# Antenna_and_LoRa.net
KiCad netlist of a schematic drawn in Altium Designer
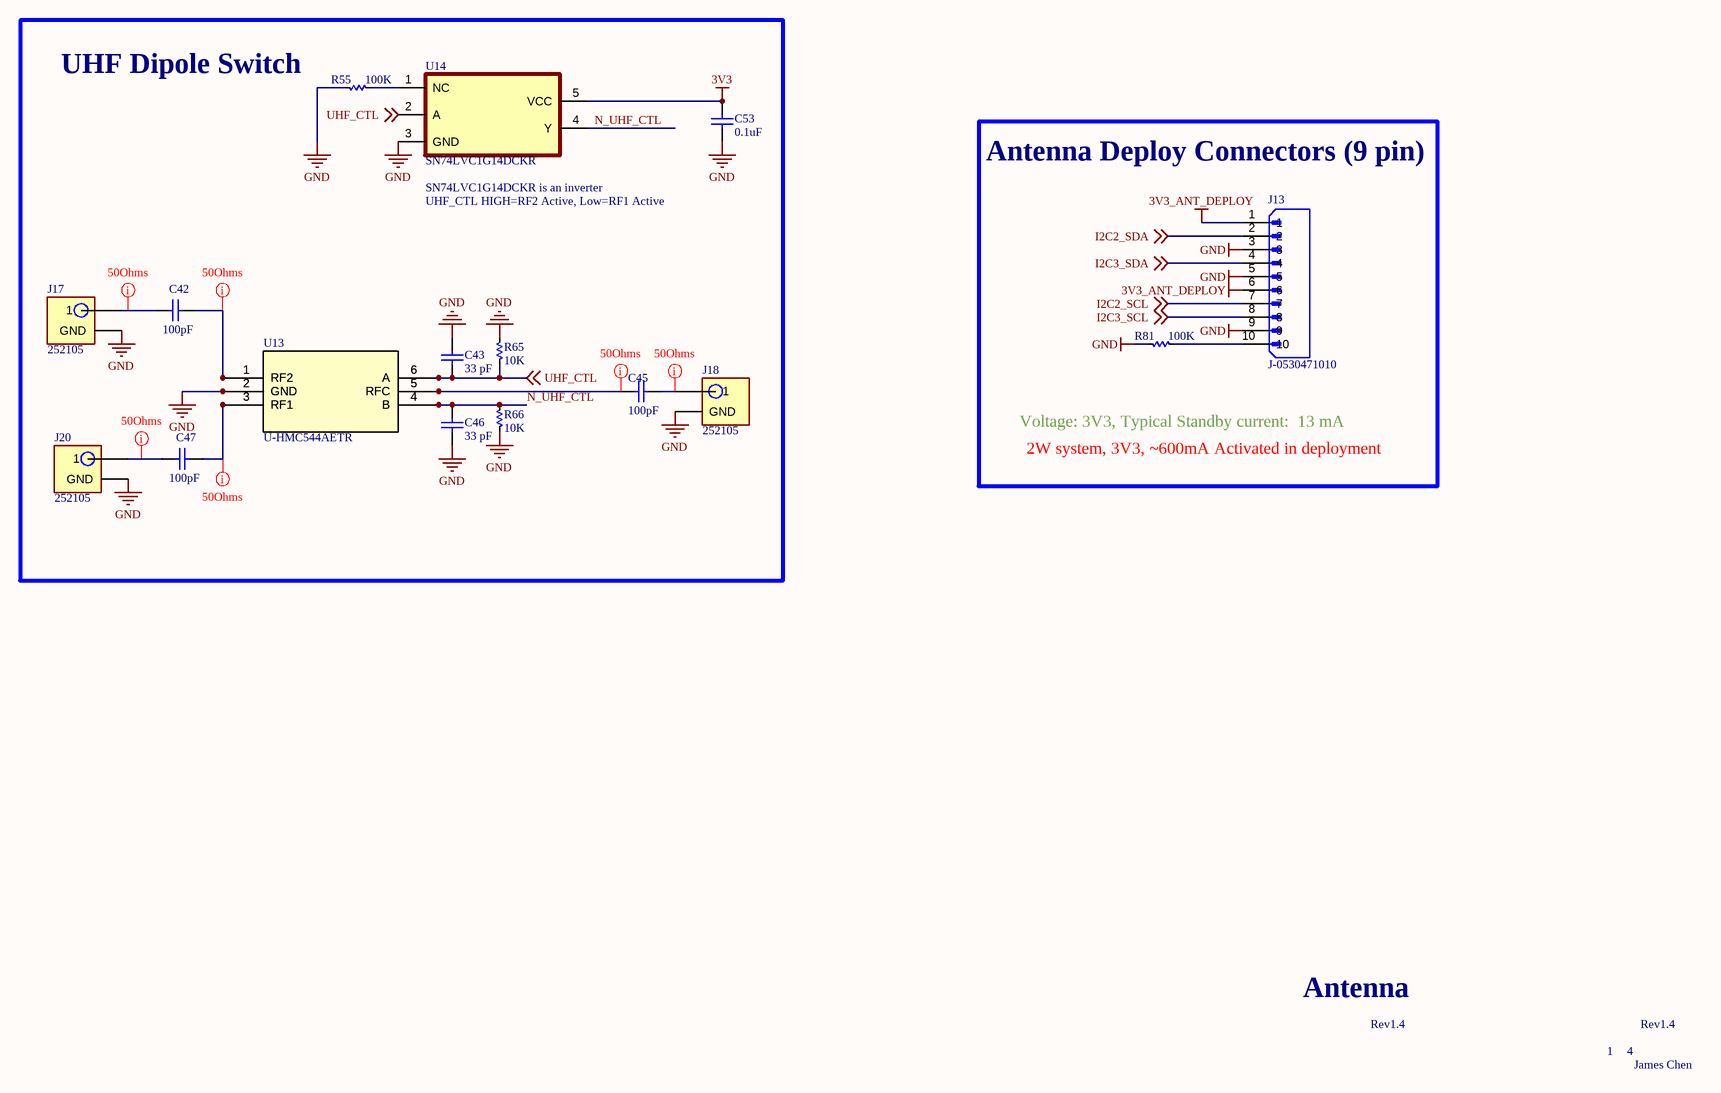
[diagram p0: Antenna and LoRa.SchDoc]

(export (version "E")
  (design (tool "Eeschema 10.0.6"))
  (components
    (comp (ref "C42")
      (value "100pF")
      (footprint "0603")
      (description "CAP CER 100PF 50V X7R 0603")
      (fields (field (name "DISTRIBUTOR PART #") "311-3601-1-ND") (field (name "MANUFACTURER") "YAGEO"))
      (libsource (lib "RS2D") (part "CC-108-K-50V-X7R-0603"))
    )
    (comp (ref "C43")
      (value "33 pF")
      (footprint "0603")
      (description "CAP CER 33PF 50V X7R 0603")
      (fields
        (field (name "DISTRIBUTOR PART #") "399-C0603C330K5RAC7867CT-ND")
        (field (name "MANUFACTURER") "KEMET")
      )
      (libsource (lib "OBC Development Board") (part "CC-339-K-50V-X7R-0603"))
    )
    (comp (ref "C45")
      (value "100pF")
      (footprint "0603")
      (description "CAP CER 100PF 50V X7R 0603")
      (fields (field (name "DISTRIBUTOR PART #") "311-3601-1-ND") (field (name "MANUFACTURER") "YAGEO"))
      (libsource (lib "RS2D") (part "CC-108-K-50V-X7R-0603"))
    )
    (comp (ref "C46")
      (value "33 pF")
      (footprint "0603")
      (description "CAP CER 33PF 50V X7R 0603")
      (fields
        (field (name "DISTRIBUTOR PART #") "399-C0603C330K5RAC7867CT-ND")
        (field (name "MANUFACTURER") "KEMET")
      )
      (libsource (lib "OBC Development Board") (part "CC-339-K-50V-X7R-0603"))
    )
    (comp (ref "C47")
      (value "100pF")
      (footprint "0603")
      (description "CAP CER 100PF 50V X7R 0603")
      (fields (field (name "DISTRIBUTOR PART #") "311-3601-1-ND") (field (name "MANUFACTURER") "YAGEO"))
      (libsource (lib "RS2D") (part "CC-108-K-50V-X7R-0603"))
    )
    (comp (ref "C53")
      (value "0.1uF")
      (footprint "0603")
      (description "25V 100nF X7R ±10% 0603 Multilayer Ceramic Capacitors MLCC - SMD/SMT ROHS")
      (fields
        (field (name "DISTRIBUTOR PART #") "C354391")
        (field (name "MANUFACTURER") "Murata Electronics")
      )
      (libsource (lib "OBC Development Board") (part "CC-100nF-25V-X7R-0603"))
    )
    (comp (ref "J13")
      (value "J-0530471010")
      (footprint "J-0530471010")
      (description "CONN HEADER VERT 10POS 1.25MM")
      (fields (field (name "MANUFACTURER") "Molex") (field (name "MANUFACTURER PART #") "0530471010"))
      (libsource (lib "OBC Development Board") (part "J-0530471010"))
    )
    (comp (ref "J17")
      (value "252105")
      (footprint "J-252105")
      (description "CONN MCX RCPT STR 50 OHM PCB")
      (fields (field (name "MANUFACTURER") "Amphenol RF") (field (name "DISTRIBUTOR PART #") "ACX1262-ND"))
      (libsource (lib "OBC Development Board") (part "J-252105"))
    )
    (comp (ref "J18")
      (value "252105")
      (footprint "J-252105")
      (description "CONN MCX RCPT STR 50 OHM PCB")
      (fields (field (name "MANUFACTURER") "Amphenol RF") (field (name "DISTRIBUTOR PART #") "ACX1262-ND"))
      (libsource (lib "") (part "J-252105_1"))
    )
    (comp (ref "J20")
      (value "252105")
      (footprint "J-252105")
      (description "CONN MCX RCPT STR 50 OHM PCB")
      (fields (field (name "MANUFACTURER") "Amphenol RF") (field (name "DISTRIBUTOR PART #") "ACX1262-ND"))
      (libsource (lib "OBC Development Board") (part "J-252105"))
    )
    (comp (ref "R55")
      (value "100K")
      (footprint "0603")
      (description "RES SMD 100KΩ 0.1% 1/16W 0603")
      (fields
        (field (name "DISTRIBUTOR PART #") "A119912CT-ND")
        (field (name "MANUFACTURER") "TE Connectivity")
      )
      (libsource (lib "OBC Development Board") (part "RT-100K0-F-1/16W-0603"))
    )
    (comp (ref "R65")
      (value "10K")
      (footprint "0603")
      (description "10 kOhms ±0.1% 0.063W, 1/16W Chip Resistor 0603 (1608 Metric) - Thin Film")
      (fields
        (field (name "DISTRIBUTOR PART #") "A119886CT-ND")
        (field (name "MANUFACTURER") "TE Connectivity Passive Product")
      )
      (libsource (lib "OBC Development Board") (part "RT-10K0-F-1/16W-0603"))
    )
    (comp (ref "R66")
      (value "10K")
      (footprint "0603")
      (description "10 kOhms ±0.1% 0.063W, 1/16W Chip Resistor 0603 (1608 Metric) - Thin Film")
      (fields
        (field (name "DISTRIBUTOR PART #") "A119886CT-ND")
        (field (name "MANUFACTURER") "TE Connectivity Passive Product")
      )
      (libsource (lib "OBC Development Board") (part "RT-10K0-F-1/16W-0603"))
    )
    (comp (ref "R81")
      (value "100K")
      (footprint "0603")
      (description "RES SMD 100KΩ 0.1% 1/16W 0603")
      (fields
        (field (name "DISTRIBUTOR PART #") "A119912CT-ND")
        (field (name "MANUFACTURER") "TE Connectivity")
      )
      (libsource (lib "OBC Development Board") (part "RT-100K0-F-1/16W-0603"))
    )
    (comp (ref "U13")
      (value "U-HMC544AETR")
      (footprint "U-HMC544AETR")
      (description "0Hz~4GHz 23dB 0.7dB SOT-23-6 RF Switches ROHS")
      (fields
        (field (name "MANUFACTURER") "Analog Devices")
        (field (name "MANUFACTURER PART #") "HMC544AETR")
      )
      (libsource (lib "OBC Development Board") (part "U-HMC544AETR"))
    )
    (comp (ref "U14")
      (value "SN74LVC1G14DCKR")
      (footprint "U-SN74LVC1G14DCKR")
      (description "IC INVERT SCHMITT 1CH 1IN SC70")
      (fields
        (field (name "MANUFACTURER") "Texas Instruments")
        (field (name "DISTRIBUTOR PART #") "296-11608-1-ND")
      )
      (libsource (lib "OBC Development Board") (part "U-SN74LVC1G14DCKR"))
    )
  )
  (nets
    (net (code "1") (name "/N_UHF_CTL") (class "Default")
      (node (ref "C46") (pin "2") (pinfunction "2_2") (pintype "passive"))
      (node (ref "R66") (pin "2") (pintype "passive"))
      (node (ref "U13") (pin "4") (pinfunction "B_4") (pintype "passive"))
      (node (ref "U14") (pin "4") (pinfunction "Y_4") (pintype "passive"))
    )
    (net (code "2") (name "3V3") (class "Default")
      (node (ref "C53") (pin "2") (pinfunction "2_2") (pintype "passive"))
      (node (ref "U14") (pin "5") (pinfunction "VCC_5") (pintype "passive"))
    )
    (net (code "3") (name "3V3_ANT_DEPLOY") (class "Default")
      (node (ref "J13") (pin "1") (pinfunction "1_1") (pintype "passive"))
      (node (ref "J13") (pin "6") (pinfunction "6_6") (pintype "passive"))
    )
    (net (code "4") (name "GND") (class "Default")
      (node (ref "C43") (pin "2") (pinfunction "2_2") (pintype "passive"))
      (node (ref "C46") (pin "1") (pinfunction "1_1") (pintype "passive"))
      (node (ref "C53") (pin "1") (pinfunction "1_1") (pintype "passive"))
      (node (ref "J13") (pin "3") (pinfunction "3_3") (pintype "passive"))
      (node (ref "J13") (pin "5") (pinfunction "5_5") (pintype "passive"))
      (node (ref "J13") (pin "9") (pinfunction "9_9") (pintype "passive"))
      (node (ref "J17") (pin "0") (pinfunction "GND_0") (pintype "passive"))
      (node (ref "J18") (pin "0") (pinfunction "GND_0") (pintype "passive"))
      (node (ref "J20") (pin "0") (pinfunction "GND_0") (pintype "passive"))
      (node (ref "R55") (pin "1") (pintype "passive"))
      (node (ref "R65") (pin "2") (pintype "passive"))
      (node (ref "R66") (pin "1") (pintype "passive"))
      (node (ref "R81") (pin "1") (pintype "passive"))
      (node (ref "U13") (pin "2") (pinfunction "GND_2") (pintype "passive"))
      (node (ref "U14") (pin "3") (pinfunction "GND_3") (pintype "passive"))
    )
    (net (code "5") (name "I2C2_SCL") (class "Default")
      (node (ref "J13") (pin "7") (pinfunction "7_7") (pintype "passive"))
    )
    (net (code "6") (name "I2C2_SDA") (class "Default")
      (node (ref "J13") (pin "2") (pinfunction "2_2") (pintype "passive"))
    )
    (net (code "7") (name "I2C3_SCL") (class "Default")
      (node (ref "J13") (pin "8") (pinfunction "8_8") (pintype "passive"))
    )
    (net (code "8") (name "I2C3_SDA") (class "Default")
      (node (ref "J13") (pin "4") (pinfunction "4_4") (pintype "passive"))
    )
    (net (code "9") (name "Net-(C42-Pad1)") (class "Default")
      (node (ref "C42") (pin "1") (pinfunction "1_1") (pintype "passive"))
      (node (ref "J17") (pin "1") (pinfunction "1_1") (pintype "passive"))
    )
    (net (code "10") (name "Net-(C45-Pad2)") (class "Default")
      (node (ref "C45") (pin "2") (pinfunction "2_2") (pintype "passive"))
      (node (ref "J18") (pin "1") (pinfunction "1_1") (pintype "passive"))
    )
    (net (code "11") (name "Net-(C47-Pad1)") (class "Default")
      (node (ref "C47") (pin "1") (pinfunction "1_1") (pintype "passive"))
      (node (ref "J20") (pin "1") (pinfunction "1_1") (pintype "passive"))
    )
    (net (code "12") (name "Net-(J13-Pad10)") (class "Default")
      (node (ref "J13") (pin "10") (pinfunction "10_10") (pintype "passive"))
      (node (ref "R81") (pin "2") (pintype "passive"))
    )
    (net (code "13") (name "Net-(U13-RF1)") (class "Default")
      (node (ref "C47") (pin "2") (pinfunction "2_2") (pintype "passive"))
      (node (ref "U13") (pin "3") (pinfunction "RF1_3") (pintype "passive"))
    )
    (net (code "14") (name "Net-(U13-RF2)") (class "Default")
      (node (ref "C42") (pin "2") (pinfunction "2_2") (pintype "passive"))
      (node (ref "U13") (pin "1") (pinfunction "RF2_1") (pintype "passive"))
    )
    (net (code "15") (name "Net-(U13-RFC)") (class "Default")
      (node (ref "C45") (pin "1") (pinfunction "1_1") (pintype "passive"))
      (node (ref "U13") (pin "5") (pinfunction "RFC_5") (pintype "passive"))
    )
    (net (code "16") (name "Net-(U14-NC)") (class "Default")
      (node (ref "R55") (pin "2") (pintype "passive"))
      (node (ref "U14") (pin "1") (pinfunction "NC_1") (pintype "passive"))
    )
    (net (code "17") (name "UHF_CTL") (class "Default")
      (node (ref "C43") (pin "1") (pinfunction "1_1") (pintype "passive"))
      (node (ref "R65") (pin "1") (pintype "passive"))
      (node (ref "U13") (pin "6") (pinfunction "A_6") (pintype "passive"))
      (node (ref "U14") (pin "2") (pinfunction "A_2") (pintype "passive"))
    )
  )
)
